# BPMLabColumnRX.net
KiCad netlist of a schematic drawn in EAGLE
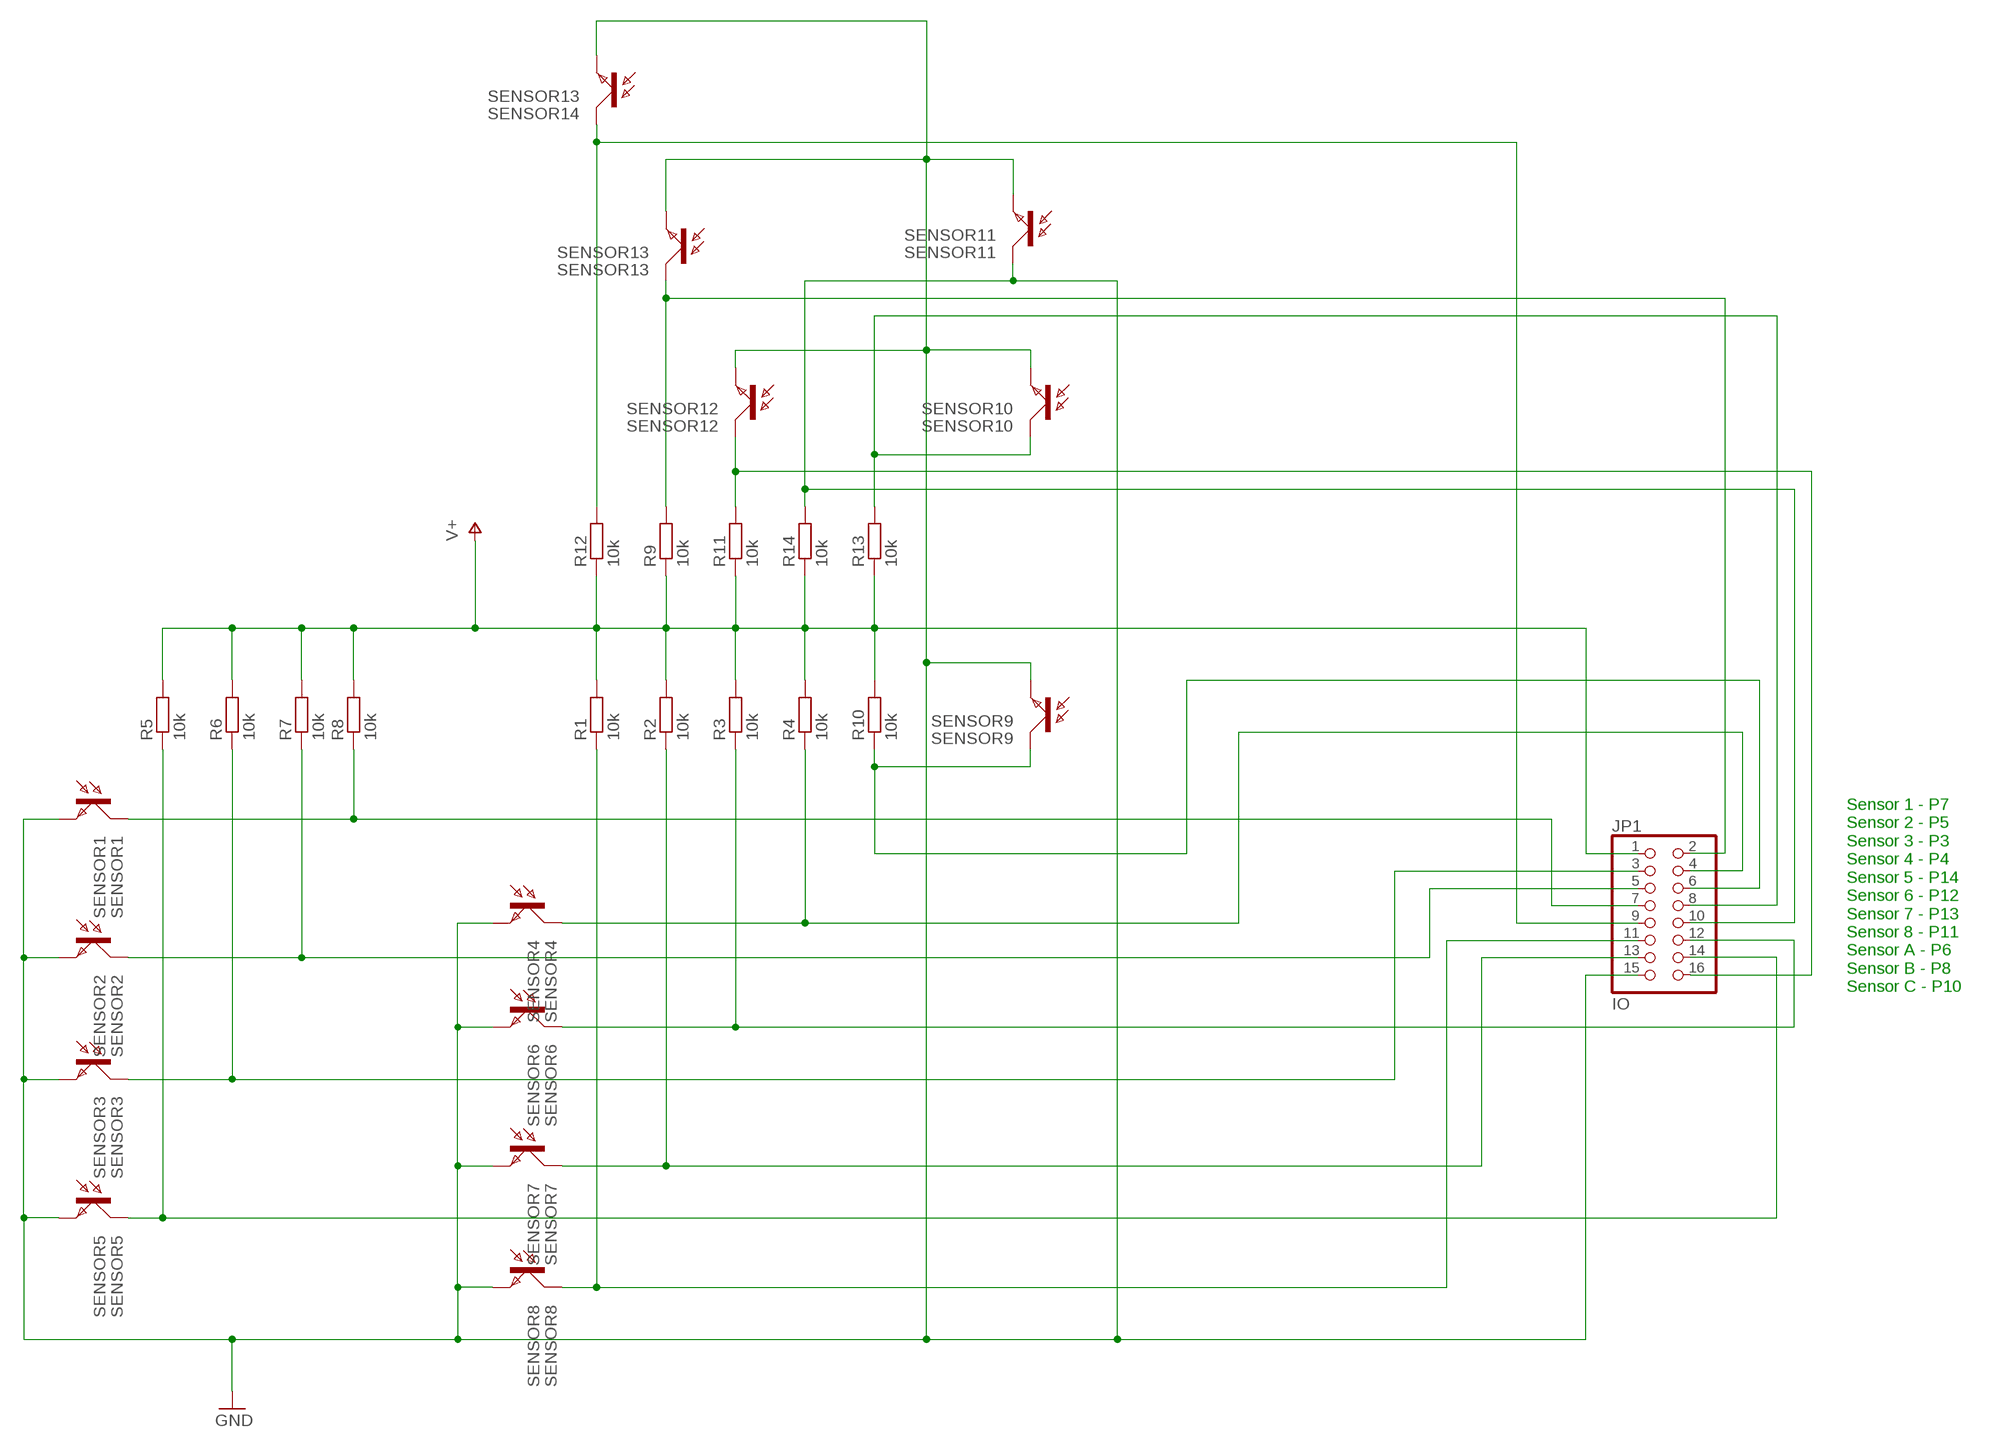
[diagram p0: schematic, sheet 1]

(export (version "E")
  (design (tool "Eeschema 10.0.6"))
  (components
    (comp (ref "JP1")
      (value "IO")
      (footprint "eagle-import:2X08")
      (libsource (lib "eagle-import") (part "PINHD-2X8"))
    )
    (comp (ref "R1")
      (value "10k")
      (footprint "eagle-import:M0805")
      (libsource (lib "eagle-import") (part "R-EU_M0805"))
    )
    (comp (ref "R2")
      (value "10k")
      (footprint "eagle-import:M0805")
      (libsource (lib "eagle-import") (part "R-EU_M0805"))
    )
    (comp (ref "R3")
      (value "10k")
      (footprint "eagle-import:M0805")
      (libsource (lib "eagle-import") (part "R-EU_M0805"))
    )
    (comp (ref "R4")
      (value "10k")
      (footprint "eagle-import:M0805")
      (libsource (lib "eagle-import") (part "R-EU_M0805"))
    )
    (comp (ref "R5")
      (value "10k")
      (footprint "eagle-import:M0805")
      (libsource (lib "eagle-import") (part "R-EU_M0805"))
    )
    (comp (ref "R6")
      (value "10k")
      (footprint "eagle-import:M0805")
      (libsource (lib "eagle-import") (part "R-EU_M0805"))
    )
    (comp (ref "R7")
      (value "10k")
      (footprint "eagle-import:M0805")
      (libsource (lib "eagle-import") (part "R-EU_M0805"))
    )
    (comp (ref "R8")
      (value "10k")
      (footprint "eagle-import:M0805")
      (libsource (lib "eagle-import") (part "R-EU_M0805"))
    )
    (comp (ref "R9")
      (value "10k")
      (footprint "eagle-import:M0805")
      (libsource (lib "eagle-import") (part "R-EU_M0805"))
    )
    (comp (ref "R10")
      (value "10k")
      (footprint "eagle-import:M0805")
      (libsource (lib "eagle-import") (part "R-EU_M0805"))
    )
    (comp (ref "R11")
      (value "10k")
      (footprint "eagle-import:M0805")
      (libsource (lib "eagle-import") (part "R-EU_M0805"))
    )
    (comp (ref "R12")
      (value "10k")
      (footprint "eagle-import:M0805")
      (libsource (lib "eagle-import") (part "R-EU_M0805"))
    )
    (comp (ref "R13")
      (value "10k")
      (footprint "eagle-import:M0805")
      (libsource (lib "eagle-import") (part "R-EU_M0805"))
    )
    (comp (ref "R14")
      (value "10k")
      (footprint "eagle-import:M0805")
      (libsource (lib "eagle-import") (part "R-EU_M0805"))
    )
    (comp (ref "SENSOR1")
      (value "SENSOR1")
      (footprint "eagle-import:BPX81")
      (libsource (lib "eagle-import") (part "BPX81"))
    )
    (comp (ref "SENSOR2")
      (value "SENSOR2")
      (footprint "eagle-import:BPX81")
      (libsource (lib "eagle-import") (part "BPX81"))
    )
    (comp (ref "SENSOR3")
      (value "SENSOR3")
      (footprint "eagle-import:BPX81")
      (libsource (lib "eagle-import") (part "BPX81"))
    )
    (comp (ref "SENSOR4")
      (value "SENSOR4")
      (footprint "eagle-import:BPX81")
      (libsource (lib "eagle-import") (part "BPX81"))
    )
    (comp (ref "SENSOR5")
      (value "SENSOR5")
      (footprint "eagle-import:BPX81")
      (libsource (lib "eagle-import") (part "BPX81"))
    )
    (comp (ref "SENSOR6")
      (value "SENSOR6")
      (footprint "eagle-import:BPX81")
      (libsource (lib "eagle-import") (part "BPX81"))
    )
    (comp (ref "SENSOR7")
      (value "SENSOR7")
      (footprint "eagle-import:BPX81")
      (libsource (lib "eagle-import") (part "BPX81"))
    )
    (comp (ref "SENSOR8")
      (value "SENSOR8")
      (footprint "eagle-import:BPX81")
      (libsource (lib "eagle-import") (part "BPX81"))
    )
    (comp (ref "SENSOR9")
      (value "SENSOR9")
      (footprint "eagle-import:BPX81")
      (libsource (lib "eagle-import") (part "BPX81"))
    )
    (comp (ref "SENSOR10")
      (value "SENSOR10")
      (footprint "eagle-import:BPX81")
      (libsource (lib "eagle-import") (part "BPX81"))
    )
    (comp (ref "SENSOR11")
      (value "SENSOR11")
      (footprint "eagle-import:BPX81")
      (libsource (lib "eagle-import") (part "BPX81"))
    )
    (comp (ref "SENSOR12")
      (value "SENSOR12")
      (footprint "eagle-import:BPX81")
      (libsource (lib "eagle-import") (part "BPX81"))
    )
    (comp (ref "SENSOR13")
      (value "SENSOR13")
      (footprint "eagle-import:BPX81")
      (libsource (lib "eagle-import") (part "BPX81"))
    )
    (comp (ref "SENSOR14")
      (value "SENSOR13")
      (footprint "eagle-import:BPX81")
      (libsource (lib "eagle-import") (part "BPX81"))
    )
  )
  (nets
    (net (code "1") (name "GND") (class "Default")
      (node (ref "JP1") (pin "10") (pinfunction "10_10") (pintype "passive"))
      (node (ref "JP1") (pin "15") (pinfunction "15_15") (pintype "passive"))
      (node (ref "R14") (pin "2") (pinfunction "2_2") (pintype "passive"))
      (node (ref "SENSOR1") (pin "E") (pinfunction "E_E") (pintype "passive"))
      (node (ref "SENSOR10") (pin "E") (pinfunction "E_E") (pintype "passive"))
      (node (ref "SENSOR11") (pin "C") (pinfunction "C_C") (pintype "passive"))
      (node (ref "SENSOR11") (pin "E") (pinfunction "E_E") (pintype "passive"))
      (node (ref "SENSOR12") (pin "E") (pinfunction "E_E") (pintype "passive"))
      (node (ref "SENSOR13") (pin "E") (pinfunction "E_E") (pintype "passive"))
      (node (ref "SENSOR14") (pin "E") (pinfunction "E_E") (pintype "passive"))
      (node (ref "SENSOR2") (pin "E") (pinfunction "E_E") (pintype "passive"))
      (node (ref "SENSOR3") (pin "E") (pinfunction "E_E") (pintype "passive"))
      (node (ref "SENSOR4") (pin "E") (pinfunction "E_E") (pintype "passive"))
      (node (ref "SENSOR5") (pin "E") (pinfunction "E_E") (pintype "passive"))
      (node (ref "SENSOR6") (pin "E") (pinfunction "E_E") (pintype "passive"))
      (node (ref "SENSOR7") (pin "E") (pinfunction "E_E") (pintype "passive"))
      (node (ref "SENSOR8") (pin "E") (pinfunction "E_E") (pintype "passive"))
      (node (ref "SENSOR9") (pin "E") (pinfunction "E_E") (pintype "passive"))
    )
    (net (code "2") (name "Net-(JP1-Pad2)") (class "Default")
      (node (ref "JP1") (pin "2") (pinfunction "2_2") (pintype "passive"))
      (node (ref "R9") (pin "2") (pinfunction "2_2") (pintype "passive"))
      (node (ref "SENSOR13") (pin "C") (pinfunction "C_C") (pintype "passive"))
    )
    (net (code "3") (name "Net-(JP1-Pad3)") (class "Default")
      (node (ref "JP1") (pin "3") (pinfunction "3_3") (pintype "passive"))
      (node (ref "R6") (pin "1") (pinfunction "1_1") (pintype "passive"))
      (node (ref "SENSOR3") (pin "C") (pinfunction "C_C") (pintype "passive"))
    )
    (net (code "4") (name "Net-(JP1-Pad4)") (class "Default")
      (node (ref "JP1") (pin "4") (pinfunction "4_4") (pintype "passive"))
      (node (ref "R4") (pin "1") (pinfunction "1_1") (pintype "passive"))
      (node (ref "SENSOR4") (pin "C") (pinfunction "C_C") (pintype "passive"))
    )
    (net (code "5") (name "Net-(JP1-Pad5)") (class "Default")
      (node (ref "JP1") (pin "5") (pinfunction "5_5") (pintype "passive"))
      (node (ref "R7") (pin "1") (pinfunction "1_1") (pintype "passive"))
      (node (ref "SENSOR2") (pin "C") (pinfunction "C_C") (pintype "passive"))
    )
    (net (code "6") (name "Net-(JP1-Pad6)") (class "Default")
      (node (ref "JP1") (pin "6") (pinfunction "6_6") (pintype "passive"))
      (node (ref "R10") (pin "1") (pinfunction "1_1") (pintype "passive"))
      (node (ref "SENSOR9") (pin "C") (pinfunction "C_C") (pintype "passive"))
    )
    (net (code "7") (name "Net-(JP1-Pad7)") (class "Default")
      (node (ref "JP1") (pin "7") (pinfunction "7_7") (pintype "passive"))
      (node (ref "R8") (pin "1") (pinfunction "1_1") (pintype "passive"))
      (node (ref "SENSOR1") (pin "C") (pinfunction "C_C") (pintype "passive"))
    )
    (net (code "8") (name "Net-(JP1-Pad8)") (class "Default")
      (node (ref "JP1") (pin "8") (pinfunction "8_8") (pintype "passive"))
      (node (ref "R13") (pin "2") (pinfunction "2_2") (pintype "passive"))
      (node (ref "SENSOR10") (pin "C") (pinfunction "C_C") (pintype "passive"))
    )
    (net (code "9") (name "Net-(JP1-Pad9)") (class "Default")
      (node (ref "JP1") (pin "9") (pinfunction "9_9") (pintype "passive"))
      (node (ref "R12") (pin "2") (pinfunction "2_2") (pintype "passive"))
      (node (ref "SENSOR14") (pin "C") (pinfunction "C_C") (pintype "passive"))
    )
    (net (code "10") (name "Net-(JP1-Pad11)") (class "Default")
      (node (ref "JP1") (pin "11") (pinfunction "11_11") (pintype "passive"))
      (node (ref "R1") (pin "1") (pinfunction "1_1") (pintype "passive"))
      (node (ref "SENSOR8") (pin "C") (pinfunction "C_C") (pintype "passive"))
    )
    (net (code "11") (name "Net-(JP1-Pad12)") (class "Default")
      (node (ref "JP1") (pin "12") (pinfunction "12_12") (pintype "passive"))
      (node (ref "R3") (pin "1") (pinfunction "1_1") (pintype "passive"))
      (node (ref "SENSOR6") (pin "C") (pinfunction "C_C") (pintype "passive"))
    )
    (net (code "12") (name "Net-(JP1-Pad13)") (class "Default")
      (node (ref "JP1") (pin "13") (pinfunction "13_13") (pintype "passive"))
      (node (ref "R2") (pin "1") (pinfunction "1_1") (pintype "passive"))
      (node (ref "SENSOR7") (pin "C") (pinfunction "C_C") (pintype "passive"))
    )
    (net (code "13") (name "Net-(JP1-Pad14)") (class "Default")
      (node (ref "JP1") (pin "14") (pinfunction "14_14") (pintype "passive"))
      (node (ref "R5") (pin "1") (pinfunction "1_1") (pintype "passive"))
      (node (ref "SENSOR5") (pin "C") (pinfunction "C_C") (pintype "passive"))
    )
    (net (code "14") (name "Net-(JP1-Pad16)") (class "Default")
      (node (ref "JP1") (pin "16") (pinfunction "16_16") (pintype "passive"))
      (node (ref "R11") (pin "2") (pinfunction "2_2") (pintype "passive"))
      (node (ref "SENSOR12") (pin "C") (pinfunction "C_C") (pintype "passive"))
    )
    (net (code "15") (name "V+") (class "Default")
      (node (ref "JP1") (pin "1") (pinfunction "1_1") (pintype "passive"))
      (node (ref "R1") (pin "2") (pinfunction "2_2") (pintype "passive"))
      (node (ref "R10") (pin "2") (pinfunction "2_2") (pintype "passive"))
      (node (ref "R11") (pin "1") (pinfunction "1_1") (pintype "passive"))
      (node (ref "R12") (pin "1") (pinfunction "1_1") (pintype "passive"))
      (node (ref "R13") (pin "1") (pinfunction "1_1") (pintype "passive"))
      (node (ref "R14") (pin "1") (pinfunction "1_1") (pintype "passive"))
      (node (ref "R2") (pin "2") (pinfunction "2_2") (pintype "passive"))
      (node (ref "R3") (pin "2") (pinfunction "2_2") (pintype "passive"))
      (node (ref "R4") (pin "2") (pinfunction "2_2") (pintype "passive"))
      (node (ref "R5") (pin "2") (pinfunction "2_2") (pintype "passive"))
      (node (ref "R6") (pin "2") (pinfunction "2_2") (pintype "passive"))
      (node (ref "R7") (pin "2") (pinfunction "2_2") (pintype "passive"))
      (node (ref "R8") (pin "2") (pinfunction "2_2") (pintype "passive"))
      (node (ref "R9") (pin "1") (pinfunction "1_1") (pintype "passive"))
    )
  )
)
